# Controle_Cupula.net
KiCad netlist of a schematic drawn in Altium Designer
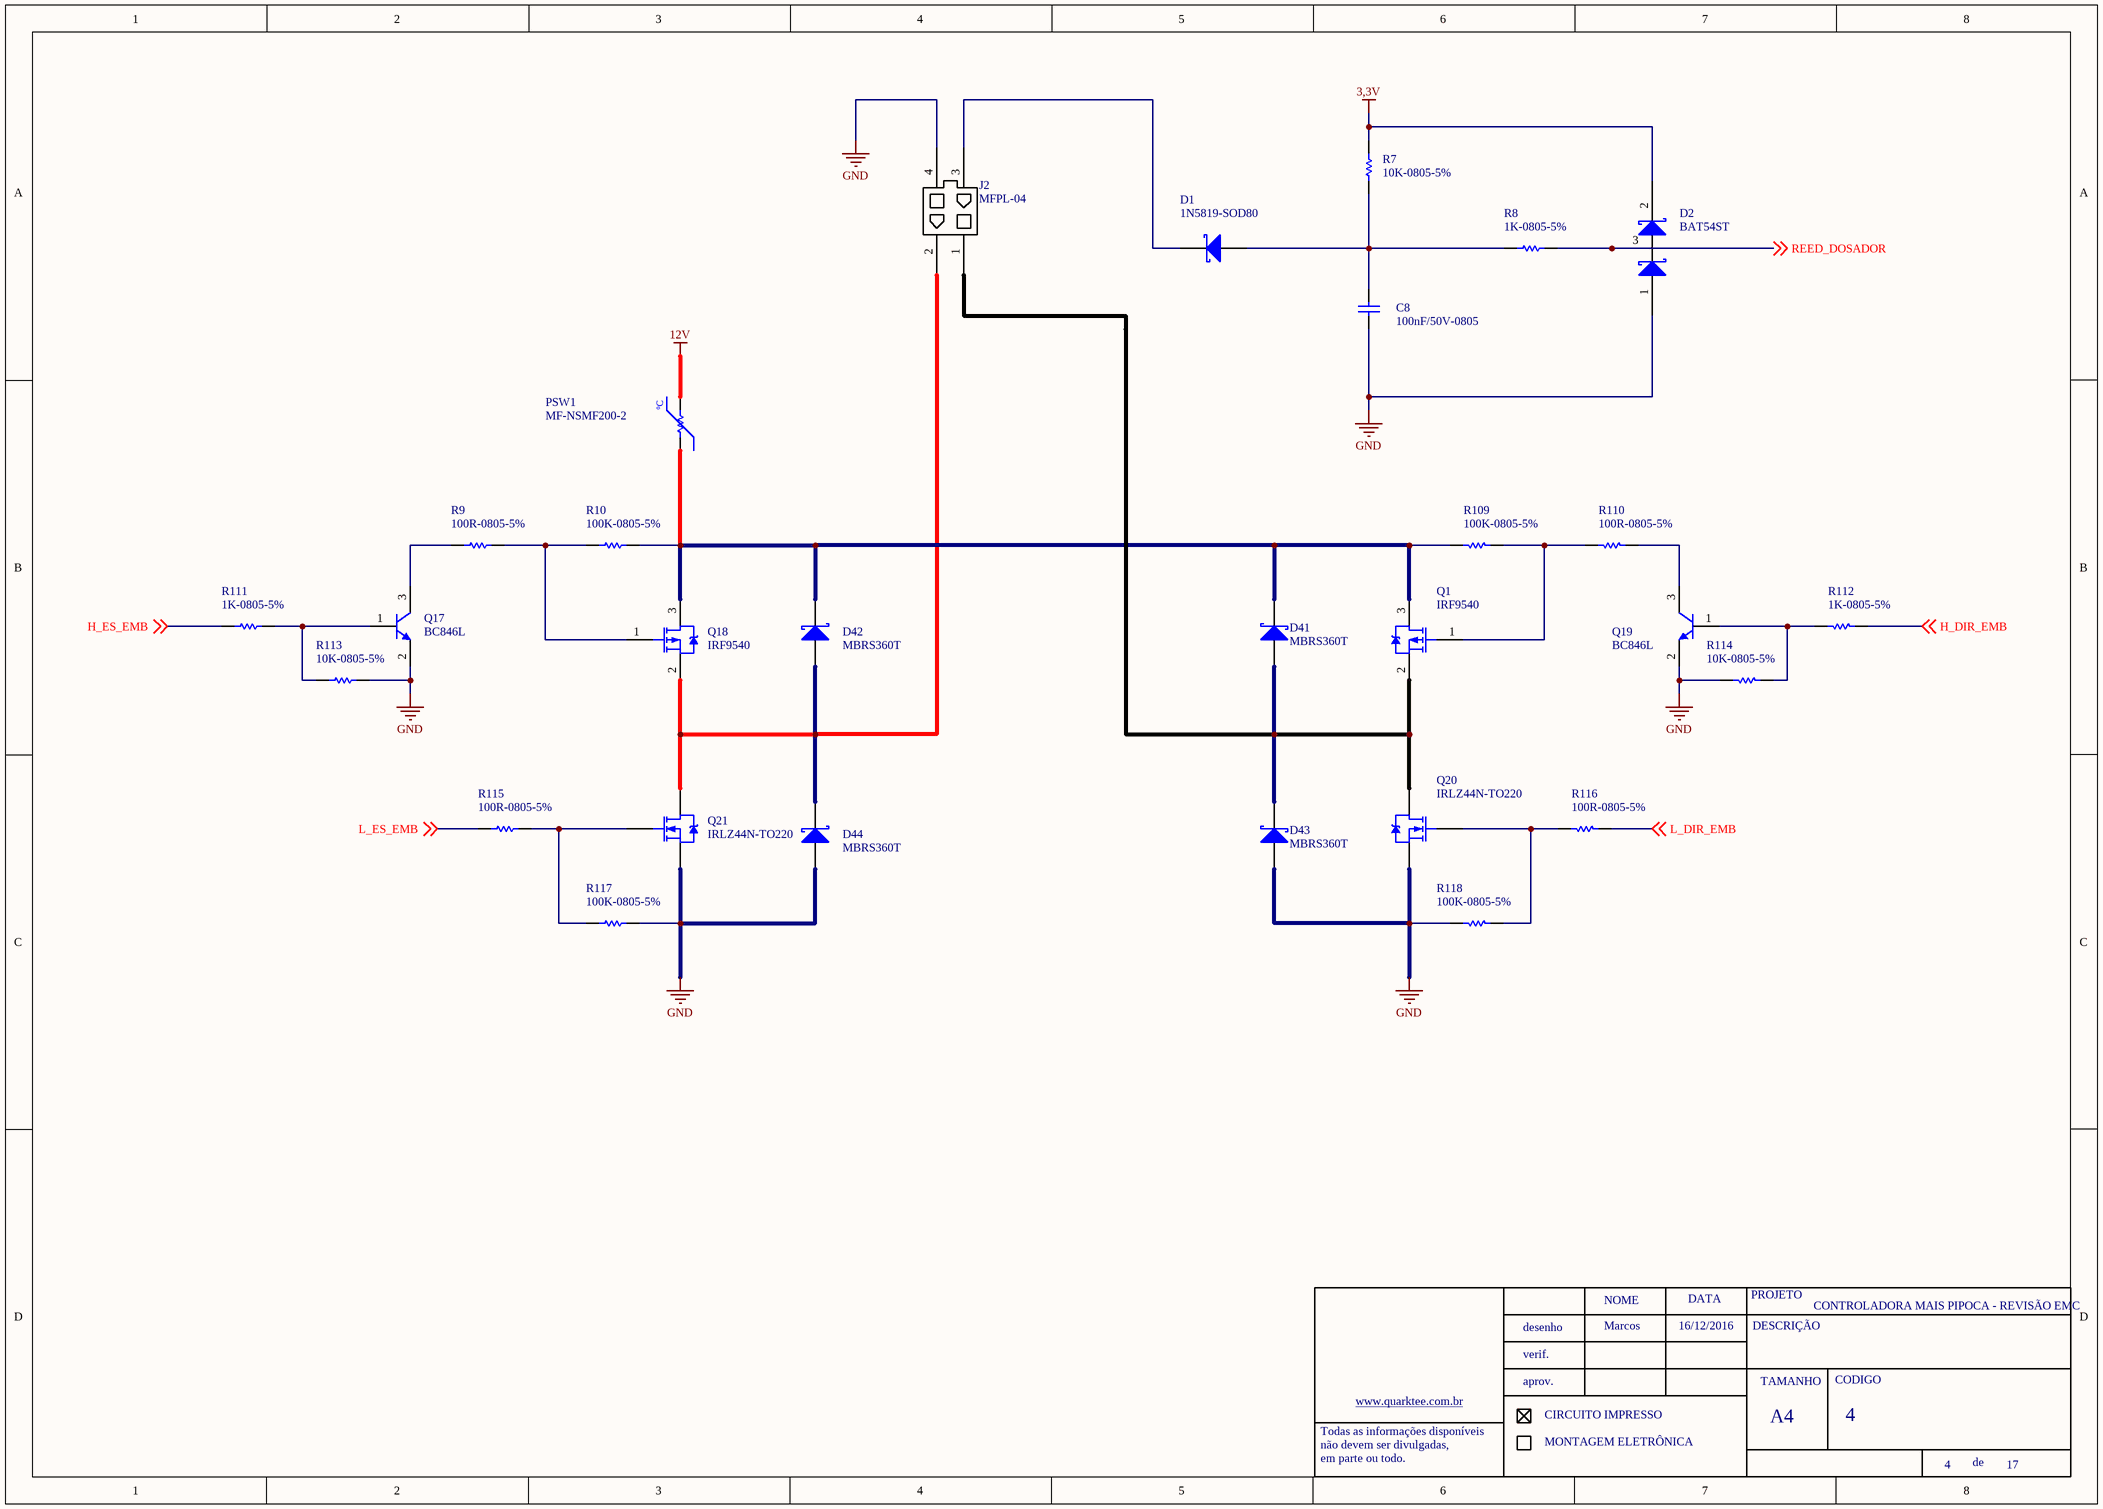
[diagram p0: Controle_Cupula.SchDoc]

(export (version "E")
  (design (tool "Eeschema 10.0.6"))
  (components
    (comp (ref "C8")
      (value "100nF/50V-0805")
      (footprint "0805-REVISADO ONDA")
      (libsource (lib "AquinoLib") (part "100nF/50-0805-NPO"))
    )
    (comp (ref "D1")
      (value "1N5819-SOD80")
      (footprint "MINIMLEF/SOD80 - REVISADO ONDA")
      (libsource (lib "AquinoLib") (part "1N5819-SOD80"))
    )
    (comp (ref "D2")
      (value "BAT54ST")
      (footprint "SOT23 - REVISADO ONDA")
      (libsource (lib "AquinoLib") (part "BAT54ST"))
    )
    (comp (ref "D41")
      (value "MBRS360T")
      (footprint "DO-214AB")
      (description "1N5819-SOD80")
      (libsource (lib "AquinoLib") (part "1N5819-SOD80"))
    )
    (comp (ref "D42")
      (value "MBRS360T")
      (footprint "DO-214AB")
      (description "1N5819-SOD80")
      (libsource (lib "AquinoLib") (part "1N5819-SOD80"))
    )
    (comp (ref "D43")
      (value "MBRS360T")
      (footprint "DO-214AB")
      (description "1N5819-SOD80")
      (libsource (lib "AquinoLib") (part "1N5819-SOD80"))
    )
    (comp (ref "D44")
      (value "MBRS360T")
      (footprint "DO-214AB")
      (description "1N5819-SOD80")
      (libsource (lib "AquinoLib") (part "1N5819-SOD80"))
    )
    (comp (ref "J2") (value "MFPL-04") (libsource (lib "AquinoLib") (part "MFPL-04")))
    (comp (ref "PSW1")
      (value "MF-NSMF200-2")
      (footprint "1206-REVISADO ONDA")
      (description "NANOSMDC020F-2")
      (libsource (lib "AquinoLib") (part "POLYSWITCH 200mA"))
    )
    (comp (ref "Q1")
      (value "IRF9540")
      (footprint "TO220-3 EM PÉ")
      (libsource (lib "ChaveDigital3") (part "IRF9540"))
    )
    (comp (ref "Q17")
      (value "BC846L")
      (footprint "SOT23 - REVISADO ONDA")
      (libsource (lib "AquinoLib") (part "BC846"))
    )
    (comp (ref "Q18")
      (value "IRF9540")
      (footprint "TO220-3 EM PÉ")
      (libsource (lib "ChaveDigital3") (part "IRF9540"))
    )
    (comp (ref "Q19")
      (value "BC846L")
      (footprint "SOT23 - REVISADO ONDA")
      (libsource (lib "AquinoLib") (part "BC846"))
    )
    (comp (ref "Q20")
      (value "IRLZ44N-TO220")
      (footprint "TO220-3 EM PÉ")
      (libsource (lib "ChaveDigital3") (part "IRLZ44N-TO220"))
    )
    (comp (ref "Q21")
      (value "IRLZ44N-TO220")
      (footprint "TO220-3 EM PÉ")
      (libsource (lib "ChaveDigital3") (part "IRLZ44N-TO220"))
    )
    (comp (ref "R7")
      (value "10K-0805-5%")
      (footprint "0805-REVISADO ONDA")
      (libsource (lib "AquinoLib") (part "10K-0805-5%"))
    )
    (comp (ref "R8")
      (value "1K-0805-5%")
      (footprint "0805-REVISADO ONDA")
      (libsource (lib "AquinoLib") (part "1K-0805-5%"))
    )
    (comp (ref "R9")
      (value "100R-0805-5%")
      (footprint "0805-REVISADO ONDA")
      (description "1K-0805-5%")
      (libsource (lib "AquinoLib") (part "1K-0805-5%"))
    )
    (comp (ref "R10")
      (value "100K-0805-5%")
      (footprint "0805-REVISADO ONDA")
      (libsource (lib "AquinoLib") (part "100K-0805-5%"))
    )
    (comp (ref "R109")
      (value "100K-0805-5%")
      (footprint "0805-REVISADO ONDA")
      (libsource (lib "AquinoLib") (part "100K-0805-5%"))
    )
    (comp (ref "R110")
      (value "100R-0805-5%")
      (footprint "0805-REVISADO ONDA")
      (description "1K-0805-5%")
      (libsource (lib "AquinoLib") (part "1K-0805-5%"))
    )
    (comp (ref "R111")
      (value "1K-0805-5%")
      (footprint "0805-REVISADO ONDA")
      (description "10K-0805-5%")
      (libsource (lib "AquinoLib") (part "10K-0805-5%"))
    )
    (comp (ref "R112")
      (value "1K-0805-5%")
      (footprint "0805-REVISADO ONDA")
      (description "10K-0805-5%")
      (libsource (lib "AquinoLib") (part "10K-0805-5%"))
    )
    (comp (ref "R113")
      (value "10K-0805-5%")
      (footprint "0805-REVISADO ONDA")
      (libsource (lib "AquinoLib") (part "10K-0805-5%"))
    )
    (comp (ref "R114")
      (value "10K-0805-5%")
      (footprint "0805-REVISADO ONDA")
      (libsource (lib "AquinoLib") (part "10K-0805-5%"))
    )
    (comp (ref "R115")
      (value "100R-0805-5%")
      (footprint "0805-REVISADO ONDA")
      (libsource (lib "AquinoLib") (part "100R-0805-5%"))
    )
    (comp (ref "R116")
      (value "100R-0805-5%")
      (footprint "0805-REVISADO ONDA")
      (libsource (lib "AquinoLib") (part "100R-0805-5%"))
    )
    (comp (ref "R117")
      (value "100K-0805-5%")
      (footprint "0805-REVISADO ONDA")
      (libsource (lib "AquinoLib") (part "100K-0805-5%"))
    )
    (comp (ref "R118")
      (value "100K-0805-5%")
      (footprint "0805-REVISADO ONDA")
      (libsource (lib "AquinoLib") (part "100K-0805-5%"))
    )
  )
  (nets
    (net (code "1") (name "3,3V") (class "Default")
      (node (ref "D2") (pin "2") (pinfunction "2_2") (pintype "passive"))
      (node (ref "R7") (pin "2") (pinfunction "2_2") (pintype "passive"))
    )
    (net (code "2") (name "12V") (class "Default")
      (node (ref "PSW1") (pin "2") (pinfunction "2_2") (pintype "passive"))
    )
    (net (code "3") (name "GND") (class "Default")
      (node (ref "C8") (pin "1") (pinfunction "1_1") (pintype "passive"))
      (node (ref "D2") (pin "1") (pinfunction "1_1") (pintype "passive"))
      (node (ref "D43") (pin "1") (pinfunction "A_1") (pintype "passive"))
      (node (ref "D44") (pin "1") (pinfunction "A_1") (pintype "passive"))
      (node (ref "J2") (pin "4") (pinfunction "4_4") (pintype "passive"))
      (node (ref "Q17") (pin "2") (pinfunction "E_2") (pintype "passive"))
      (node (ref "Q19") (pin "2") (pinfunction "E_2") (pintype "passive"))
      (node (ref "Q20") (pin "3") (pinfunction "S_3") (pintype "passive"))
      (node (ref "Q21") (pin "3") (pinfunction "S_3") (pintype "passive"))
      (node (ref "R113") (pin "2") (pinfunction "2_2") (pintype "passive"))
      (node (ref "R114") (pin "2") (pinfunction "2_2") (pintype "passive"))
      (node (ref "R117") (pin "2") (pinfunction "2_2") (pintype "passive"))
      (node (ref "R118") (pin "2") (pinfunction "2_2") (pintype "passive"))
    )
    (net (code "4") (name "H_DIR_EMB") (class "Default")
      (node (ref "R112") (pin "1") (pinfunction "1_1") (pintype "passive"))
    )
    (net (code "5") (name "H_ES_EMB") (class "Default")
      (node (ref "R111") (pin "1") (pinfunction "1_1") (pintype "passive"))
    )
    (net (code "6") (name "L_DIR_EMB") (class "Default")
      (node (ref "R116") (pin "1") (pinfunction "1_1") (pintype "passive"))
    )
    (net (code "7") (name "L_ES_EMB") (class "Default")
      (node (ref "R115") (pin "1") (pinfunction "1_1") (pintype "passive"))
    )
    (net (code "8") (name "Net-(D1-A)") (class "Default")
      (node (ref "C8") (pin "2") (pinfunction "2_2") (pintype "passive"))
      (node (ref "D1") (pin "1") (pinfunction "A_1") (pintype "passive"))
      (node (ref "R7") (pin "1") (pinfunction "1_1") (pintype "passive"))
      (node (ref "R8") (pin "1") (pinfunction "1_1") (pintype "passive"))
    )
    (net (code "9") (name "Net-(D1-K)") (class "Default")
      (node (ref "D1") (pin "2") (pinfunction "K_2") (pintype "passive"))
      (node (ref "J2") (pin "3") (pinfunction "3_3") (pintype "passive"))
    )
    (net (code "10") (name "Net-(D41-A)") (class "Default")
      (node (ref "D41") (pin "1") (pinfunction "A_1") (pintype "passive"))
      (node (ref "D43") (pin "2") (pinfunction "K_2") (pintype "passive"))
      (node (ref "J2") (pin "1") (pinfunction "1_1") (pintype "passive"))
      (node (ref "Q1") (pin "2") (pinfunction "DRENO_2") (pintype "passive"))
      (node (ref "Q20") (pin "2") (pinfunction "D_2") (pintype "passive"))
    )
    (net (code "11") (name "Net-(D41-K)") (class "Default")
      (node (ref "D41") (pin "2") (pinfunction "K_2") (pintype "passive"))
      (node (ref "D42") (pin "2") (pinfunction "K_2") (pintype "passive"))
      (node (ref "PSW1") (pin "1") (pinfunction "1_1") (pintype "passive"))
      (node (ref "Q1") (pin "3") (pinfunction "SOURCE_3") (pintype "passive"))
      (node (ref "Q18") (pin "3") (pinfunction "SOURCE_3") (pintype "passive"))
      (node (ref "R10") (pin "2") (pinfunction "2_2") (pintype "passive"))
      (node (ref "R109") (pin "2") (pinfunction "2_2") (pintype "passive"))
    )
    (net (code "12") (name "Net-(D42-A)") (class "Default")
      (node (ref "D42") (pin "1") (pinfunction "A_1") (pintype "passive"))
      (node (ref "D44") (pin "2") (pinfunction "K_2") (pintype "passive"))
      (node (ref "J2") (pin "2") (pinfunction "2_2") (pintype "passive"))
      (node (ref "Q18") (pin "2") (pinfunction "DRENO_2") (pintype "passive"))
      (node (ref "Q21") (pin "2") (pinfunction "D_2") (pintype "passive"))
    )
    (net (code "13") (name "Net-(Q1-GATE)") (class "Default")
      (node (ref "Q1") (pin "1") (pinfunction "GATE_1") (pintype "passive"))
      (node (ref "R109") (pin "1") (pinfunction "1_1") (pintype "passive"))
      (node (ref "R110") (pin "2") (pinfunction "2_2") (pintype "passive"))
    )
    (net (code "14") (name "Net-(Q17-B)") (class "Default")
      (node (ref "Q17") (pin "1") (pinfunction "B_1") (pintype "passive"))
      (node (ref "R111") (pin "2") (pinfunction "2_2") (pintype "passive"))
      (node (ref "R113") (pin "1") (pinfunction "1_1") (pintype "passive"))
    )
    (net (code "15") (name "Net-(Q17-C)") (class "Default")
      (node (ref "Q17") (pin "3") (pinfunction "C_3") (pintype "passive"))
      (node (ref "R9") (pin "1") (pinfunction "1_1") (pintype "passive"))
    )
    (net (code "16") (name "Net-(Q18-GATE)") (class "Default")
      (node (ref "Q18") (pin "1") (pinfunction "GATE_1") (pintype "passive"))
      (node (ref "R10") (pin "1") (pinfunction "1_1") (pintype "passive"))
      (node (ref "R9") (pin "2") (pinfunction "2_2") (pintype "passive"))
    )
    (net (code "17") (name "Net-(Q19-B)") (class "Default")
      (node (ref "Q19") (pin "1") (pinfunction "B_1") (pintype "passive"))
      (node (ref "R112") (pin "2") (pinfunction "2_2") (pintype "passive"))
      (node (ref "R114") (pin "1") (pinfunction "1_1") (pintype "passive"))
    )
    (net (code "18") (name "Net-(Q19-C)") (class "Default")
      (node (ref "Q19") (pin "3") (pinfunction "C_3") (pintype "passive"))
      (node (ref "R110") (pin "1") (pinfunction "1_1") (pintype "passive"))
    )
    (net (code "19") (name "Net-(Q20-G)") (class "Default")
      (node (ref "Q20") (pin "1") (pinfunction "G_1") (pintype "passive"))
      (node (ref "R116") (pin "2") (pinfunction "2_2") (pintype "passive"))
      (node (ref "R118") (pin "1") (pinfunction "1_1") (pintype "passive"))
    )
    (net (code "20") (name "Net-(Q21-G)") (class "Default")
      (node (ref "Q21") (pin "1") (pinfunction "G_1") (pintype "passive"))
      (node (ref "R115") (pin "2") (pinfunction "2_2") (pintype "passive"))
      (node (ref "R117") (pin "1") (pinfunction "1_1") (pintype "passive"))
    )
    (net (code "21") (name "REED_DOSADOR") (class "Default")
      (node (ref "D2") (pin "3") (pinfunction "3_3") (pintype "passive"))
      (node (ref "R8") (pin "2") (pinfunction "2_2") (pintype "passive"))
    )
  )
)
